# splitter.net
KiCad netlist of a schematic drawn in Altium Designer
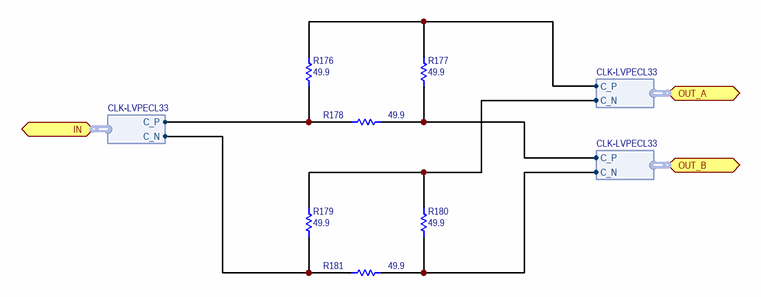
[diagram p0: splitter.SchDoc]

(export (version "E")
  (design (tool "Eeschema 10.0.6"))
  (components
    (comp (ref "R176")
      (value "49.9")
      (footprint "generic:0402")
      (description "Thin Film Resistor 49.9 ±0.1% 0402")
      (fields (field (name "MANUFACTURER") "Panasonic") (field (name "TOLERANCE") "±0.1%"))
      (libsource (lib "Graviton") (part "RES 0402"))
    )
    (comp (ref "R177")
      (value "49.9")
      (footprint "generic:0402")
      (description "Thin Film Resistor 49.9 ±0.1% 0402")
      (fields (field (name "MANUFACTURER") "Panasonic") (field (name "TOLERANCE") "±0.1%"))
      (libsource (lib "Graviton") (part "RES 0402"))
    )
    (comp (ref "R178")
      (value "49.9")
      (footprint "generic:0402")
      (description "Thin Film Resistor 49.9 ±0.1% 0402")
      (fields (field (name "MANUFACTURER") "Panasonic") (field (name "TOLERANCE") "±0.1%"))
      (libsource (lib "Graviton") (part "RES 0402"))
    )
    (comp (ref "R179")
      (value "49.9")
      (footprint "generic:0402")
      (description "Thin Film Resistor 49.9 ±0.1% 0402")
      (fields (field (name "MANUFACTURER") "Panasonic") (field (name "TOLERANCE") "±0.1%"))
      (libsource (lib "Graviton") (part "RES 0402"))
    )
    (comp (ref "R180")
      (value "49.9")
      (footprint "generic:0402")
      (description "Thin Film Resistor 49.9 ±0.1% 0402")
      (fields (field (name "MANUFACTURER") "Panasonic") (field (name "TOLERANCE") "±0.1%"))
      (libsource (lib "Graviton") (part "RES 0402"))
    )
    (comp (ref "R181")
      (value "49.9")
      (footprint "generic:0402")
      (description "Thin Film Resistor 49.9 ±0.1% 0402")
      (fields (field (name "MANUFACTURER") "Panasonic") (field (name "TOLERANCE") "±0.1%"))
      (libsource (lib "Graviton") (part "RES 0402"))
    )
  )
  (nets
    (net (code "3") (name "Net-(R176-Pad1)") (class "Default")
      (node (ref "R176") (pin "1") (pinfunction "1_1") (pintype "passive"))
      (node (ref "R177") (pin "1") (pinfunction "1_1") (pintype "passive"))
    )
    (net (code "4") (name "Net-(R176-Pad2)") (class "Default")
      (node (ref "R176") (pin "2") (pinfunction "2_2") (pintype "passive"))
      (node (ref "R178") (pin "2") (pinfunction "2_2") (pintype "passive"))
    )
    (net (code "5") (name "Net-(R177-Pad2)") (class "Default")
      (node (ref "R177") (pin "2") (pinfunction "2_2") (pintype "passive"))
      (node (ref "R178") (pin "1") (pinfunction "1_1") (pintype "passive"))
    )
    (net (code "6") (name "Net-(R179-Pad1)") (class "Default")
      (node (ref "R179") (pin "1") (pinfunction "1_1") (pintype "passive"))
      (node (ref "R180") (pin "1") (pinfunction "1_1") (pintype "passive"))
    )
    (net (code "7") (name "Net-(R179-Pad2)") (class "Default")
      (node (ref "R179") (pin "2") (pinfunction "2_2") (pintype "passive"))
      (node (ref "R181") (pin "2") (pinfunction "2_2") (pintype "passive"))
    )
    (net (code "8") (name "Net-(R180-Pad2)") (class "Default")
      (node (ref "R180") (pin "2") (pinfunction "2_2") (pintype "passive"))
      (node (ref "R181") (pin "1") (pinfunction "1_1") (pintype "passive"))
    )
  )
)
